# USBFTDI_I2C_V2.net
KiCad netlist of a schematic drawn in EAGLE
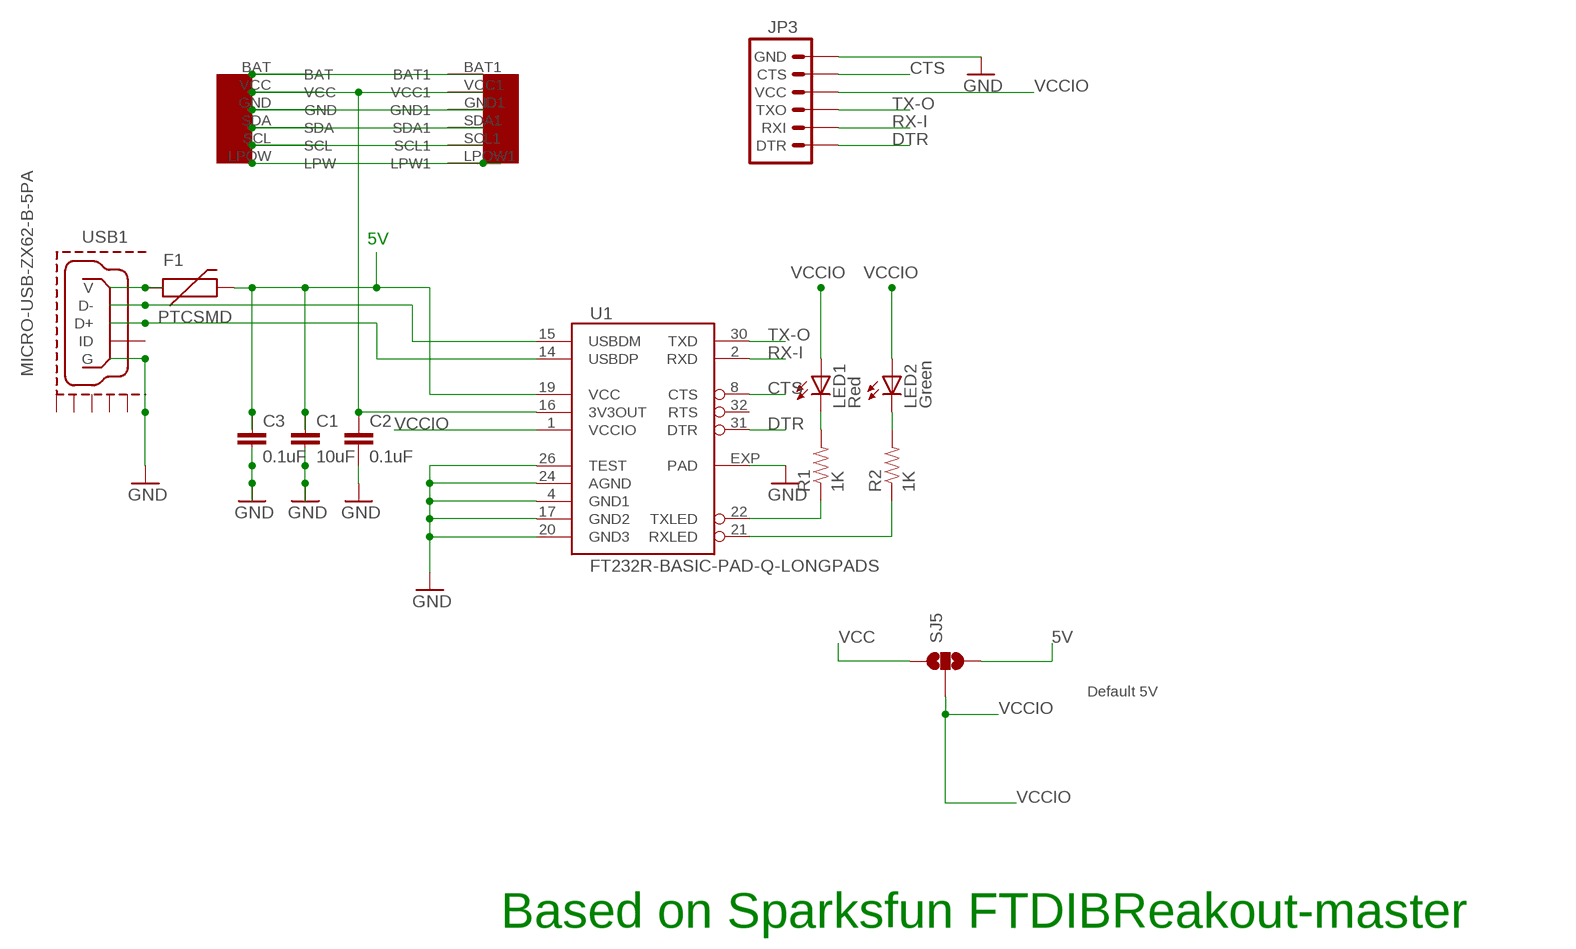
[diagram p0: schematic, sheet 1]

(export (version "E")
  (design (tool "Eeschema 10.0.6"))
  (components
    (comp (ref "C1")
      (value "10uF")
      (footprint "eagle-import:0402-CAP")
      (libsource (lib "eagle-import") (part "CAP-0402"))
    )
    (comp (ref "C2")
      (value "0.1uF")
      (footprint "eagle-import:0402-CAP")
      (libsource (lib "eagle-import") (part "CAP-0402"))
    )
    (comp (ref "C3")
      (value "0.1uF")
      (footprint "eagle-import:0402-CAP")
      (libsource (lib "eagle-import") (part "CAP-0402"))
    )
    (comp (ref "F1")
      (value "PTCSMD")
      (footprint "eagle-import:PTC-1206")
      (libsource (lib "eagle-import") (part "PTCSMD"))
    )
    (comp (ref "JP3")
      (value "ARDUINO_SERIAL_PROGRAMPTH")
      (footprint "eagle-import:1X06")
      (libsource (lib "eagle-import") (part "ARDUINO_SERIAL_PROGRAMPTH"))
    )
    (comp (ref "LED1")
      (value "Red")
      (footprint "eagle-import:LED-0603")
      (libsource (lib "eagle-import") (part "LED0603"))
    )
    (comp (ref "LED2")
      (value "Green")
      (footprint "eagle-import:LED-0603")
      (libsource (lib "eagle-import") (part "LED0603"))
    )
    (comp (ref "R1")
      (value "1K")
      (footprint "eagle-import:R0402")
      (libsource (lib "eagle-import") (part "RESISTOR-0402"))
    )
    (comp (ref "R2")
      (value "1K")
      (footprint "eagle-import:R0402")
      (libsource (lib "eagle-import") (part "RESISTOR-0402"))
    )
    (comp (ref "SJ5")
      (value "SOLDERJUMPER_2WAY-LEFT-BRIDGED")
      (footprint "eagle-import:SJ-3-LEFT")
      (libsource (lib "eagle-import") (part "SOLDERJUMPER_2WAY-LEFT-BRIDGED"))
    )
    (comp (ref "U$1")
      (value "EZ-I2CHEADERV1")
      (footprint "eagle-import:EZ-I2CHEADERV1")
      (libsource (lib "eagle-import") (part "EZ-I2CHEADERV1"))
    )
    (comp (ref "U1")
      (value "FT232R-BASIC-PAD-Q-LONGPADS")
      (footprint "eagle-import:QFN32-LONG")
      (libsource (lib "eagle-import") (part "FT232R-BASIC-PAD-Q-LONGPADS"))
    )
    (comp (ref "USB1")
      (value "MICRO-USB-ZX62-B-5PA")
      (footprint "eagle-import:ZX62-B-5PA")
      (libsource (lib "eagle-import") (part "MICRO-USB-ZX62-B-5PA"))
    )
  )
  (nets
    (net (code "1") (name "/5V") (class "Default")
      (node (ref "C1") (pin "1") (pinfunction "1_1") (pintype "passive"))
      (node (ref "C3") (pin "1") (pinfunction "1_1") (pintype "passive"))
      (node (ref "F1") (pin "2") (pinfunction "2_2") (pintype "bidirectional"))
      (node (ref "SJ5") (pin "3") (pinfunction "3_3") (pintype "passive"))
      (node (ref "U1") (pin "19") (pinfunction "VCC_19") (pintype "power_in"))
    )
    (net (code "2") (name "/CTS") (class "Default")
      (node (ref "JP3") (pin "5") (pinfunction "CTS_5") (pintype "passive"))
      (node (ref "U1") (pin "8") (pinfunction "CTS_8") (pintype "bidirectional"))
    )
    (net (code "3") (name "/DTR") (class "Default")
      (node (ref "JP3") (pin "1") (pinfunction "DTR_1") (pintype "passive"))
      (node (ref "U1") (pin "31") (pinfunction "DTR_31") (pintype "bidirectional"))
    )
    (net (code "4") (name "/GND1") (class "Default")
      (node (ref "USB1") (pin "GND@1") (pinfunction "GND1_GND@1") (pintype "power_in"))
    )
    (net (code "5") (name "/GND2") (class "Default")
      (node (ref "USB1") (pin "GND@2") (pinfunction "GND2_GND@2") (pintype "power_in"))
    )
    (net (code "6") (name "/GND3") (class "Default")
      (node (ref "USB1") (pin "GND@3") (pinfunction "GND3_GND@3") (pintype "power_in"))
    )
    (net (code "7") (name "/GND4") (class "Default")
      (node (ref "USB1") (pin "GND@4") (pinfunction "GND4_GND@4") (pintype "power_in"))
    )
    (net (code "8") (name "/GND5") (class "Default")
      (node (ref "USB1") (pin "GND@5") (pinfunction "GND5_GND@5") (pintype "power_in"))
    )
    (net (code "9") (name "/RX-I") (class "Default")
      (node (ref "JP3") (pin "2") (pinfunction "RXI_2") (pintype "passive"))
      (node (ref "U1") (pin "2") (pinfunction "RXD_2") (pintype "input"))
    )
    (net (code "10") (name "/TX-O") (class "Default")
      (node (ref "JP3") (pin "3") (pinfunction "TXO_3") (pintype "passive"))
      (node (ref "U1") (pin "30") (pinfunction "TXD_30") (pintype "output"))
    )
    (net (code "11") (name "/VCC") (class "Default")
      (node (ref "C2") (pin "1") (pinfunction "1_1") (pintype "passive"))
      (node (ref "SJ5") (pin "1") (pinfunction "1_1") (pintype "passive"))
      (node (ref "U$1") (pin "VCC") (pinfunction "VCC_VCC") (pintype "bidirectional"))
      (node (ref "U$1") (pin "VCC1") (pinfunction "VCC1_VCC1") (pintype "bidirectional"))
      (node (ref "U1") (pin "16") (pinfunction "3V3OUT_16") (pintype "output"))
    )
    (net (code "12") (name "/VCCIO") (class "Default")
      (node (ref "JP3") (pin "4") (pinfunction "VCC_4") (pintype "passive"))
      (node (ref "LED1") (pin "A") (pinfunction "A_A") (pintype "passive"))
      (node (ref "LED2") (pin "A") (pinfunction "A_A") (pintype "passive"))
      (node (ref "SJ5") (pin "2") (pinfunction "2_2") (pintype "passive"))
      (node (ref "U1") (pin "1") (pinfunction "VCCIO_1") (pintype "power_in"))
    )
    (net (code "13") (name "GND") (class "Default")
      (node (ref "C1") (pin "2") (pinfunction "2_2") (pintype "passive"))
      (node (ref "C2") (pin "2") (pinfunction "2_2") (pintype "passive"))
      (node (ref "C3") (pin "2") (pinfunction "2_2") (pintype "passive"))
      (node (ref "JP3") (pin "6") (pinfunction "GND_6") (pintype "passive"))
      (node (ref "U$1") (pin "GND") (pinfunction "GND_GND") (pintype "bidirectional"))
      (node (ref "U$1") (pin "GND1") (pinfunction "GND1_GND1") (pintype "bidirectional"))
      (node (ref "U1") (pin "17") (pinfunction "GND2_17") (pintype "power_in"))
      (node (ref "U1") (pin "20") (pinfunction "GND3_20") (pintype "power_in"))
      (node (ref "U1") (pin "24") (pinfunction "AGND_24") (pintype "power_in"))
      (node (ref "U1") (pin "26") (pinfunction "TEST_26") (pintype "input"))
      (node (ref "U1") (pin "4") (pinfunction "GND1_4") (pintype "power_in"))
      (node (ref "U1") (pin "EXP") (pinfunction "PAD_EXP") (pintype "bidirectional"))
      (node (ref "USB1") (pin "5") (pinfunction "G_5") (pintype "input"))
      (node (ref "USB1") (pin "GND@6") (pinfunction "GND6_GND@6") (pintype "power_in"))
    )
    (net (code "14") (name "Net-(LED1-PadC)") (class "Default")
      (node (ref "LED1") (pin "C") (pinfunction "C_C") (pintype "passive"))
      (node (ref "R1") (pin "2") (pinfunction "2_2") (pintype "passive"))
    )
    (net (code "15") (name "Net-(LED2-PadC)") (class "Default")
      (node (ref "LED2") (pin "C") (pinfunction "C_C") (pintype "passive"))
      (node (ref "R2") (pin "2") (pinfunction "2_2") (pintype "passive"))
    )
    (net (code "16") (name "Net-(U$1-LPW)") (class "Default")
      (node (ref "U$1") (pin "LPOW") (pinfunction "LPW_LPOW") (pintype "bidirectional"))
      (node (ref "U$1") (pin "LPOW1") (pinfunction "LPW1_LPOW1") (pintype "bidirectional"))
    )
    (net (code "17") (name "Net-(U$1-PadBAT)") (class "Default")
      (node (ref "U$1") (pin "BAT") (pinfunction "BAT_BAT") (pintype "bidirectional"))
      (node (ref "U$1") (pin "BAT1") (pinfunction "BAT1_BAT1") (pintype "bidirectional"))
    )
    (net (code "18") (name "Net-(U$1-PadSCL)") (class "Default")
      (node (ref "U$1") (pin "SCL") (pinfunction "SCL_SCL") (pintype "bidirectional"))
      (node (ref "U$1") (pin "SCL1") (pinfunction "SCL1_SCL1") (pintype "bidirectional"))
    )
    (net (code "19") (name "Net-(U$1-PadSDA)") (class "Default")
      (node (ref "U$1") (pin "SDA") (pinfunction "SDA_SDA") (pintype "bidirectional"))
      (node (ref "U$1") (pin "SDA1") (pinfunction "SDA1_SDA1") (pintype "bidirectional"))
    )
    (net (code "20") (name "Net-(U1-RXLED)") (class "Default")
      (node (ref "R2") (pin "1") (pinfunction "1_1") (pintype "passive"))
      (node (ref "U1") (pin "21") (pinfunction "RXLED_21") (pintype "bidirectional"))
    )
    (net (code "21") (name "Net-(U1-TXLED)") (class "Default")
      (node (ref "R1") (pin "1") (pinfunction "1_1") (pintype "passive"))
      (node (ref "U1") (pin "22") (pinfunction "TXLED_22") (pintype "bidirectional"))
    )
    (net (code "22") (name "Net-(U1-USBDM)") (class "Default")
      (node (ref "U1") (pin "15") (pinfunction "USBDM_15") (pintype "bidirectional"))
      (node (ref "USB1") (pin "2") (pinfunction "D-_2") (pintype "input"))
    )
    (net (code "23") (name "Net-(U1-USBDP)") (class "Default")
      (node (ref "U1") (pin "14") (pinfunction "USBDP_14") (pintype "bidirectional"))
      (node (ref "USB1") (pin "3") (pinfunction "D+_3") (pintype "input"))
    )
    (net (code "24") (name "Net-(USB1-V)") (class "Default")
      (node (ref "F1") (pin "1") (pinfunction "1_1") (pintype "bidirectional"))
      (node (ref "USB1") (pin "1") (pinfunction "V_1") (pintype "input"))
    )
    (net (code "25") (name "unconnected-(U1-RTS-Pad32)") (class "Default")
      (node (ref "U1") (pin "32") (pinfunction "RTS_32") (pintype "bidirectional"))
    )
    (net (code "26") (name "unconnected-(USB1-ID-Pad4)") (class "Default")
      (node (ref "USB1") (pin "4") (pinfunction "ID_4") (pintype "input"))
    )
  )
)
